# RodManipulator_SCH.net
KiCad netlist of a schematic drawn in Altium Designer
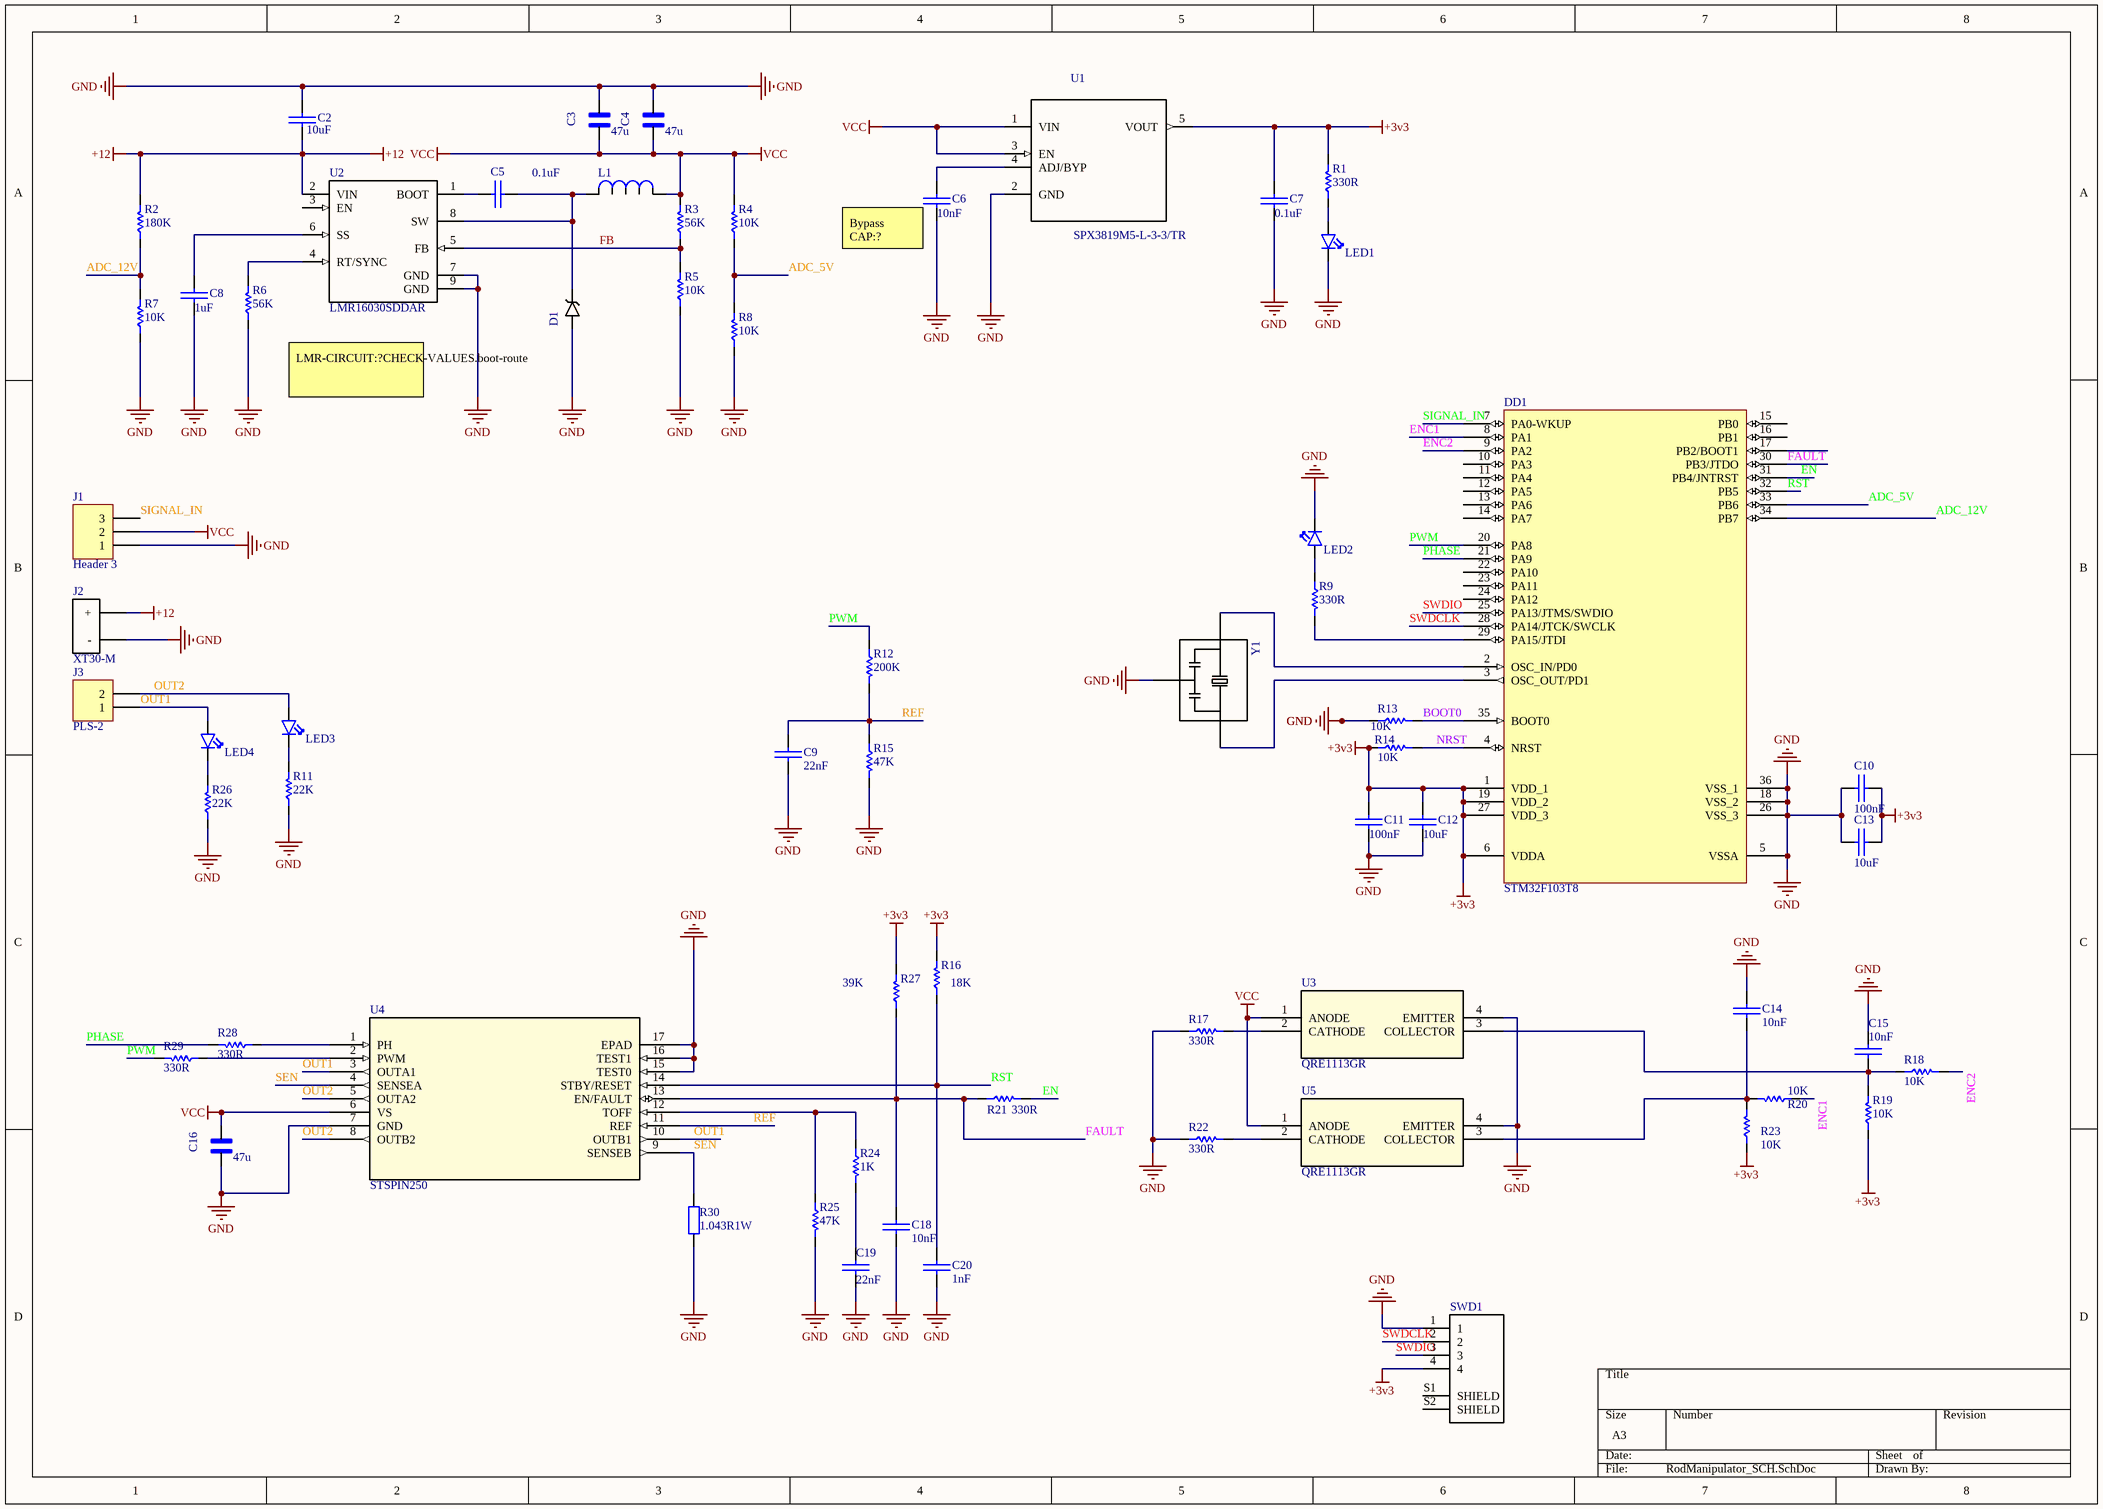
[diagram p0: RodManipulator_SCH.SchDoc]

(export (version "E")
  (design (tool "Eeschema 10.0.6"))
  (components
    (comp (ref "C2")
      (value "10uF")
      (footprint "SMD_CAP_0603")
      (description "Bipolar Capacitor")
      (fields (field (name "VOLTAGE") "100V") (field (name "DESIGNER") "Saeid Jorablo"))
      (libsource (lib "R2T Team Library") (part "Cap-Bipolar"))
    )
    (comp (ref "C3")
      (value "47u")
      (footprint "*CAPC3216X125N")
      (description "Multilayer Ceramic Capacitor, GRM Series, 47 - F, - 10%, X5R, 10 V, 1206 [3216 Metric]")
      (fields (field (name "MF") "Murata Electronics") (field (name "MP") "GRM31CR61A476KE15L"))
      (libsource (lib "lib") (part "GRM31CR61A476KE15L"))
    )
    (comp (ref "C4")
      (value "47u")
      (footprint "*CAPC3216X125N")
      (description "Multilayer Ceramic Capacitor, GRM Series, 47 - F, - 10%, X5R, 10 V, 1206 [3216 Metric]")
      (fields (field (name "MF") "Murata Electronics") (field (name "MP") "GRM31CR61A476KE15L"))
      (libsource (lib "lib") (part "GRM31CR61A476KE15L"))
    )
    (comp (ref "C5")
      (value "0.1uF")
      (footprint "SMD_CAP_0603")
      (description "Bipolar Capacitor")
      (fields (field (name "VOLTAGE") "100V") (field (name "DESIGNER") "Saeid Jorablo"))
      (libsource (lib "R2T Team Library") (part "Cap-Bipolar"))
    )
    (comp (ref "C6")
      (value "10nF")
      (footprint "SMD_CAP_0603")
      (description "Bipolar Capacitor")
      (fields (field (name "VOLTAGE") "100V") (field (name "DESIGNER") "Saeid Jorablo"))
      (libsource (lib "R2T Team Library") (part "Cap-Bipolar"))
    )
    (comp (ref "C7")
      (value "0.1uF")
      (footprint "SMD_CAP_0603")
      (description "Bipolar Capacitor")
      (fields (field (name "VOLTAGE") "100V") (field (name "DESIGNER") "Saeid Jorablo"))
      (libsource (lib "R2T Team Library") (part "Cap-Bipolar"))
    )
    (comp (ref "C8")
      (value "1uF")
      (footprint "SMD_CAP_0603")
      (description "Bipolar Capacitor")
      (fields (field (name "VOLTAGE") "100V") (field (name "DESIGNER") "Saeid Jorablo"))
      (libsource (lib "R2T Team Library") (part "Cap-Bipolar"))
    )
    (comp (ref "C9")
      (value "22nF")
      (footprint "SMD_CAP_0603")
      (description "Bipolar Capacitor")
      (fields (field (name "VOLTAGE") "100V") (field (name "DESIGNER") "Saeid Jorablo"))
      (libsource (lib "R2T Team Library") (part "Cap-Bipolar"))
    )
    (comp (ref "C10")
      (value "100nF")
      (footprint "SMD_CAP_0603")
      (description "Bipolar Capacitor")
      (fields (field (name "VOLTAGE") "100V") (field (name "DESIGNER") "Saeid Jorablo"))
      (libsource (lib "R2T Team Library") (part "Cap-Bipolar"))
    )
    (comp (ref "C11")
      (value "100nF")
      (footprint "SMD_CAP_0603")
      (description "Bipolar Capacitor")
      (fields (field (name "VOLTAGE") "100V") (field (name "DESIGNER") "Saeid Jorablo"))
      (libsource (lib "R2T Team Library") (part "Cap-Bipolar"))
    )
    (comp (ref "C12")
      (value "10uF")
      (footprint "SMD_CAP_0603")
      (description "Bipolar Capacitor")
      (fields (field (name "VOLTAGE") "100V") (field (name "DESIGNER") "Saeid Jorablo"))
      (libsource (lib "R2T Team Library") (part "Cap-Bipolar"))
    )
    (comp (ref "C13")
      (value "10uF")
      (footprint "SMD_CAP_0603")
      (description "Bipolar Capacitor")
      (fields (field (name "VOLTAGE") "100V") (field (name "DESIGNER") "Saeid Jorablo"))
      (libsource (lib "R2T Team Library") (part "Cap-Bipolar"))
    )
    (comp (ref "C14")
      (value "10nF")
      (footprint "SMD_CAP_0603")
      (description "Bipolar Capacitor")
      (fields (field (name "VOLTAGE") "100V") (field (name "DESIGNER") "Saeid Jorablo"))
      (libsource (lib "R2T Team Library") (part "Cap-Bipolar"))
    )
    (comp (ref "C15")
      (value "10nF")
      (footprint "SMD_CAP_0603")
      (description "Bipolar Capacitor")
      (fields (field (name "VOLTAGE") "100V") (field (name "DESIGNER") "Saeid Jorablo"))
      (libsource (lib "R2T Team Library") (part "Cap-Bipolar"))
    )
    (comp (ref "C16")
      (value "47u")
      (footprint "*CAPC3216X125N")
      (description "Multilayer Ceramic Capacitor, GRM Series, 47 - F, - 10%, X5R, 10 V, 1206 [3216 Metric]")
      (fields (field (name "MF") "Murata Electronics") (field (name "MP") "GRM31CR61A476KE15L"))
      (libsource (lib "lib") (part "GRM31CR61A476KE15L"))
    )
    (comp (ref "C18")
      (value "10nF")
      (footprint "SMD_CAP_0603")
      (description "Bipolar Capacitor")
      (fields (field (name "VOLTAGE") "100V") (field (name "DESIGNER") "Saeid Jorablo"))
      (libsource (lib "R2T Team Library") (part "Cap-Bipolar"))
    )
    (comp (ref "C19")
      (value "22nF")
      (footprint "SMD_CAP_0603")
      (description "Bipolar Capacitor")
      (fields (field (name "VOLTAGE") "100V") (field (name "DESIGNER") "Saeid Jorablo"))
      (libsource (lib "R2T Team Library") (part "Cap-Bipolar"))
    )
    (comp (ref "C20")
      (value "1nF")
      (footprint "SMD_CAP_0603")
      (description "Bipolar Capacitor")
      (fields (field (name "VOLTAGE") "100V") (field (name "DESIGNER") "Saeid Jorablo"))
      (libsource (lib "R2T Team Library") (part "Cap-Bipolar"))
    )
    (comp (ref "D1")
      (value "SK56")
      (footprint "*SMB_P6SMB62AT3G(Primary)")
      (description "Диод Шоттки 5А 60В [SMB / DO-214AA]")
      (fields (field (name "MF") "Littelfuse Inc."))
      (libsource (lib "lib") (part "SK56"))
    )
    (comp (ref "DD1")
      (value "STM32F103T8")
      (footprint "*QFN50P600X600X100-37N")
      (description "STM32F103T8U6, Микроконтроллер 32BIT ARM 64K FLASH [VFQFPN-36]")
      (fields (field (name "MF") "STM") (field (name "MP") "STM32F103T8U6"))
      (libsource (lib "lib") (part "STM32F103T8"))
    )
    (comp (ref "J1")
      (value "Header 3")
      (footprint "HDR Side 3 pin")
      (description "Header, 3-Pin")
      (fields (field (name "PUBLISHER") "Altium Limited"))
      (libsource (lib "lib") (part "Header 3"))
    )
    (comp (ref "J2")
      (value "XT30-M")
      (footprint "XT30-M side")
      (fields (field (name "MP") "XT60-M") (field (name "MF") "AMASS"))
      (libsource (lib "lib") (part "XT30-M"))
    )
    (comp (ref "J3")
      (value "PLS-2")
      (footprint "HDR Side 2 pin")
      (description "Header, 2-Pin")
      (fields (field (name "MF") "Connfly electronic (Zhenqin)") (field (name "MP") "PLS-3 (DS1021-1x3)"))
      (libsource (lib "lib") (part "PLS-2"))
    )
    (comp (ref "L1")
      (value "IHLP2020BZER100M01")
      (footprint "IHLP")
      (description "10µH Shielded Molded Inductor 2.3A 199mOhm Max Nonstandard")
      (fields (field (name "MF") "Vishay Dale"))
      (libsource (lib "lib") (part "IHLP2020BZER100M01"))
    )
    (comp (ref "LED1")
      (value "LED")
      (footprint "LED0603")
      (fields (field (name "DESIGNER :") "Razi Research Team Of Mashhad - Hamed Jafarzadeh"))
      (libsource (lib "R2T Team Library") (part "LED"))
    )
    (comp (ref "LED2")
      (value "LED")
      (footprint "LED0603")
      (fields (field (name "DESIGNER :") "Razi Research Team Of Mashhad - Hamed Jafarzadeh"))
      (libsource (lib "R2T Team Library") (part "LED"))
    )
    (comp (ref "LED3")
      (value "LED")
      (footprint "LED0603")
      (fields (field (name "DESIGNER :") "Razi Research Team Of Mashhad - Hamed Jafarzadeh"))
      (libsource (lib "R2T Team Library") (part "LED"))
    )
    (comp (ref "LED4")
      (value "LED")
      (footprint "LED0603")
      (fields (field (name "DESIGNER :") "Razi Research Team Of Mashhad - Hamed Jafarzadeh"))
      (libsource (lib "R2T Team Library") (part "LED"))
    )
    (comp (ref "R1")
      (value "330R")
      (footprint "RES 0603 (1608X06L)")
      (description "Resistor")
      (fields (field (name "TOLERANCE") "5%") (field (name "POWER") "1/8 W"))
      (libsource (lib "R2T Team Library") (part "Resistor"))
    )
    (comp (ref "R2")
      (value "180K")
      (footprint "RES 0603 (1608X06L)")
      (description "Resistor")
      (fields (field (name "TOLERANCE") "5%") (field (name "POWER") "1/8 W"))
      (libsource (lib "R2T Team Library") (part "Resistor"))
    )
    (comp (ref "R3")
      (value "56K")
      (footprint "RES 0603 (1608X06L)")
      (description "Resistor")
      (fields (field (name "TOLERANCE") "5%") (field (name "POWER") "1/8 W"))
      (libsource (lib "R2T Team Library") (part "Resistor"))
    )
    (comp (ref "R4")
      (value "10K")
      (footprint "RES 0603 (1608X06L)")
      (description "Resistor")
      (fields (field (name "TOLERANCE") "5%") (field (name "POWER") "1/8 W"))
      (libsource (lib "R2T Team Library") (part "Resistor"))
    )
    (comp (ref "R5")
      (value "10K")
      (footprint "RES 0603 (1608X06L)")
      (description "Resistor")
      (fields (field (name "TOLERANCE") "5%") (field (name "POWER") "1/8 W"))
      (libsource (lib "R2T Team Library") (part "Resistor"))
    )
    (comp (ref "R6")
      (value "56K")
      (footprint "RES 0603 (1608X06L)")
      (description "Resistor")
      (fields (field (name "TOLERANCE") "5%") (field (name "POWER") "1/8 W"))
      (libsource (lib "R2T Team Library") (part "Resistor"))
    )
    (comp (ref "R7")
      (value "10K")
      (footprint "RES 0603 (1608X06L)")
      (description "Resistor")
      (fields (field (name "TOLERANCE") "5%") (field (name "POWER") "1/8 W"))
      (libsource (lib "R2T Team Library") (part "Resistor"))
    )
    (comp (ref "R8")
      (value "10K")
      (footprint "RES 0603 (1608X06L)")
      (description "Resistor")
      (fields (field (name "TOLERANCE") "5%") (field (name "POWER") "1/8 W"))
      (libsource (lib "R2T Team Library") (part "Resistor"))
    )
    (comp (ref "R9")
      (value "330R")
      (footprint "RES 0603 (1608X06L)")
      (description "Resistor")
      (fields (field (name "TOLERANCE") "5%") (field (name "POWER") "1/8 W"))
      (libsource (lib "R2T Team Library") (part "Resistor"))
    )
    (comp (ref "R11")
      (value "22K")
      (footprint "RES 0603 (1608X06L)")
      (description "Resistor")
      (fields (field (name "TOLERANCE") "5%") (field (name "POWER") "1/8 W"))
      (libsource (lib "R2T Team Library") (part "Resistor"))
    )
    (comp (ref "R12")
      (value "200K")
      (footprint "RES 0603 (1608X06L)")
      (description "Resistor")
      (fields (field (name "TOLERANCE") "5%") (field (name "POWER") "1/8 W"))
      (libsource (lib "R2T Team Library") (part "Resistor"))
    )
    (comp (ref "R13")
      (value "10K")
      (footprint "RES 0603 (1608X06L)")
      (description "Resistor")
      (fields (field (name "TOLERANCE") "5%") (field (name "POWER") "1/8 W"))
      (libsource (lib "R2T Team Library") (part "Resistor"))
    )
    (comp (ref "R14")
      (value "10K")
      (footprint "RES 0603 (1608X06L)")
      (description "Resistor")
      (fields (field (name "TOLERANCE") "5%") (field (name "POWER") "1/8 W"))
      (libsource (lib "R2T Team Library") (part "Resistor"))
    )
    (comp (ref "R15")
      (value "47K")
      (footprint "RES 0603 (1608X06L)")
      (description "Resistor")
      (fields (field (name "TOLERANCE") "5%") (field (name "POWER") "1/8 W"))
      (libsource (lib "R2T Team Library") (part "Resistor"))
    )
    (comp (ref "R16")
      (value "18K")
      (footprint "RES 0603 (1608X06L)")
      (description "Resistor")
      (fields (field (name "TOLERANCE") "5%") (field (name "POWER") "1/8 W"))
      (libsource (lib "R2T Team Library") (part "Resistor"))
    )
    (comp (ref "R17")
      (value "330R")
      (footprint "RES 0603 (1608X06L)")
      (description "Resistor")
      (fields (field (name "TOLERANCE") "5%") (field (name "POWER") "1/8 W"))
      (libsource (lib "R2T Team Library") (part "Resistor"))
    )
    (comp (ref "R18")
      (value "10K")
      (footprint "RES 0603 (1608X06L)")
      (description "Resistor")
      (fields (field (name "TOLERANCE") "5%") (field (name "POWER") "1/8 W"))
      (libsource (lib "R2T Team Library") (part "Resistor"))
    )
    (comp (ref "R19")
      (value "10K")
      (footprint "RES 0603 (1608X06L)")
      (description "Resistor")
      (fields (field (name "TOLERANCE") "5%") (field (name "POWER") "1/8 W"))
      (libsource (lib "R2T Team Library") (part "Resistor"))
    )
    (comp (ref "R20")
      (value "10K")
      (footprint "RES 0603 (1608X06L)")
      (description "Resistor")
      (fields (field (name "TOLERANCE") "5%") (field (name "POWER") "1/8 W"))
      (libsource (lib "R2T Team Library") (part "Resistor"))
    )
    (comp (ref "R21")
      (value "330R")
      (footprint "RES 0603 (1608X06L)")
      (description "Resistor")
      (fields (field (name "TOLERANCE") "5%") (field (name "POWER") "1/8 W"))
      (libsource (lib "R2T Team Library") (part "Resistor"))
    )
    (comp (ref "R22")
      (value "330R")
      (footprint "RES 0603 (1608X06L)")
      (description "Resistor")
      (fields (field (name "TOLERANCE") "5%") (field (name "POWER") "1/8 W"))
      (libsource (lib "R2T Team Library") (part "Resistor"))
    )
    (comp (ref "R23")
      (value "10K")
      (footprint "RES 0603 (1608X06L)")
      (description "Resistor")
      (fields (field (name "TOLERANCE") "5%") (field (name "POWER") "1/8 W"))
      (libsource (lib "R2T Team Library") (part "Resistor"))
    )
    (comp (ref "R24")
      (value "1K")
      (footprint "RES 0603 (1608X06L)")
      (description "Resistor")
      (fields (field (name "TOLERANCE") "5%") (field (name "POWER") "1/8 W"))
      (libsource (lib "R2T Team Library") (part "Resistor"))
    )
    (comp (ref "R25")
      (value "47K")
      (footprint "RES 0603 (1608X06L)")
      (description "Resistor")
      (fields (field (name "TOLERANCE") "5%") (field (name "POWER") "1/8 W"))
      (libsource (lib "R2T Team Library") (part "Resistor"))
    )
    (comp (ref "R26")
      (value "22K")
      (footprint "RES 0603 (1608X06L)")
      (description "Resistor")
      (fields (field (name "TOLERANCE") "5%") (field (name "POWER") "1/8 W"))
      (libsource (lib "R2T Team Library") (part "Resistor"))
    )
    (comp (ref "R27")
      (value "39K")
      (footprint "RES 0603 (1608X06L)")
      (description "Resistor")
      (fields (field (name "TOLERANCE") "5%") (field (name "POWER") "1/8 W"))
      (libsource (lib "R2T Team Library") (part "Resistor"))
    )
    (comp (ref "R28")
      (value "330R")
      (footprint "RES 0603 (1608X06L)")
      (description "Resistor")
      (fields (field (name "TOLERANCE") "5%") (field (name "POWER") "1/8 W"))
      (libsource (lib "R2T Team Library") (part "Resistor"))
    )
    (comp (ref "R29")
      (value "330R")
      (footprint "RES 0603 (1608X06L)")
      (description "Resistor")
      (fields (field (name "TOLERANCE") "5%") (field (name "POWER") "1/8 W"))
      (libsource (lib "R2T Team Library") (part "Resistor"))
    )
    (comp (ref "R30")
      (value "1.043R1W")
      (footprint "RES2512")
      (description "Resistor")
      (fields (field (name "Comment") "resistor") (field (name "PUBLISHER") "Altium Limited"))
      (libsource (lib "lib") (part "resistor"))
    )
    (comp (ref "SWD1")
      (value "SM04B-GHS-TB(LF)(SN)-")
      (footprint "JST_BM04B-GHS-holes")
      (description "Conn Shrouded Header HDR 4 POS 1.25mm Solder ST SMD Reel")
      (fields (field (name "MF") "JST Sales") (field (name "MP") "SM04B-GHS-TB(LF)(SN)"))
      (libsource (lib "lib") (part "SWD SM04B-GHS-TB(LF)(SN)-"))
    )
    (comp (ref "U1")
      (value "SPX3819M5-L-3-3/TR")
      (footprint "*SOT95P280X145-5N")
      (description "Low Dropout Voltage Regulator, Adjustable 0.5A, В±1%, 2.5 to 16 Vin, 5-Pin SOT-23")
      (fields (field (name "MF") "MaxLinear, Inc."))
      (libsource (lib "lib") (part "SPX3819M5-L-3-3/TR"))
    )
    (comp (ref "U2")
      (value "LMR16030SDDAR")
      (footprint "*SOIC127P600X170-9N - duplicate")
      (fields (field (name "MF") "Texas Instruments"))
      (libsource (lib "lib") (part "LMR16030SDDAR"))
    )
    (comp (ref "U3")
      (value "QRE1113GR")
      (footprint "SMD4_2P90X3P60_ONS")
      (description "No Description Available")
      (fields (field (name "COPYRIGHT") "Copyright (C) 2018 Accelerated Designs. All rights reserved"))
      (libsource (lib "lib") (part "QRE1113GR"))
    )
    (comp (ref "U4")
      (value "STSPIN250")
      (footprint "VFQFPN-16")
      (description "No Description Available")
      (fields
        (field (name "MANUFACTURER_PART_NUMBER") "STSPIN220")
        (field (name "COPYRIGHT") "Copyright (C) 2018 Accelerated Designs. All rights reserved")
      )
      (libsource (lib "lib") (part "STSPIN250"))
    )
    (comp (ref "U5")
      (value "QRE1113GR")
      (footprint "SMD4_2P90X3P60_ONS")
      (description "No Description Available")
      (fields (field (name "COPYRIGHT") "Copyright (C) 2018 Accelerated Designs. All rights reserved"))
      (libsource (lib "lib") (part "QRE1113GR"))
    )
    (comp (ref "Y1")
      (value "CSTCE8M00G55-R0")
      (footprint "*OSC_CSTCE8M00G55-R0")
      (description "Ceramic Resonator 8MHz ??0.5% _Tol_ ??0.2% _Stability_ 33pF 40Ohm 3-Pin CSMD T/R")
      (fields (field (name "MF") "Murata"))
      (libsource (lib "lib") (part "CSTCE8M00G55-R0"))
    )
  )
  (nets
    (net (code "1") (name "+3v3") (class "Default")
      (node (ref "C10") (pin "1") (pinfunction "+_1") (pintype "passive"))
      (node (ref "C11") (pin "1") (pinfunction "+_1") (pintype "passive"))
      (node (ref "C12") (pin "1") (pinfunction "+_1") (pintype "passive"))
      (node (ref "C13") (pin "1") (pinfunction "+_1") (pintype "passive"))
      (node (ref "C7") (pin "2") (pinfunction "-_2") (pintype "passive"))
      (node (ref "DD1") (pin "1") (pinfunction "VDD_1_1") (pintype "power_in"))
      (node (ref "DD1") (pin "19") (pinfunction "VDD_2_19") (pintype "power_in"))
      (node (ref "DD1") (pin "27") (pinfunction "VDD_3_27") (pintype "power_in"))
      (node (ref "DD1") (pin "6") (pinfunction "VDDA_6") (pintype "power_in"))
      (node (ref "R1") (pin "2") (pinfunction "2_2") (pintype "passive"))
      (node (ref "R14") (pin "1") (pinfunction "1_1") (pintype "passive"))
      (node (ref "R16") (pin "2") (pinfunction "2_2") (pintype "passive"))
      (node (ref "R19") (pin "1") (pinfunction "1_1") (pintype "passive"))
      (node (ref "R23") (pin "1") (pinfunction "1_1") (pintype "passive"))
      (node (ref "R27") (pin "2") (pinfunction "2_2") (pintype "passive"))
      (node (ref "SWD1") (pin "4") (pinfunction "4_4") (pintype "passive"))
      (node (ref "U1") (pin "5") (pinfunction "VOUT_5") (pintype "output"))
    )
    (net (code "2") (name "+12") (class "Default")
      (node (ref "C2") (pin "1") (pinfunction "+_1") (pintype "passive"))
      (node (ref "J2") (pin "PLUS") (pinfunction "+_PLUS") (pintype "passive"))
      (node (ref "R2") (pin "2") (pinfunction "2_2") (pintype "passive"))
      (node (ref "U2") (pin "2") (pinfunction "VIN_2") (pintype "power_in"))
    )
    (net (code "3") (name "/ADC_5V") (class "Default")
      (node (ref "DD1") (pin "33") (pinfunction "PB6_33") (pintype "bidirectional"))
      (node (ref "R4") (pin "1") (pinfunction "1_1") (pintype "passive"))
      (node (ref "R8") (pin "2") (pinfunction "2_2") (pintype "passive"))
    )
    (net (code "4") (name "/ADC_12V") (class "Default")
      (node (ref "DD1") (pin "34") (pinfunction "PB7_34") (pintype "bidirectional"))
      (node (ref "R2") (pin "1") (pinfunction "1_1") (pintype "passive"))
      (node (ref "R7") (pin "2") (pinfunction "2_2") (pintype "passive"))
    )
    (net (code "5") (name "/BOOT0") (class "Default")
      (node (ref "DD1") (pin "35") (pinfunction "BOOT0_35") (pintype "input"))
      (node (ref "R13") (pin "2") (pinfunction "2_2") (pintype "passive"))
    )
    (net (code "6") (name "/EN") (class "Default")
      (node (ref "DD1") (pin "31") (pinfunction "PB4/JNTRST_31") (pintype "bidirectional"))
      (node (ref "R21") (pin "2") (pinfunction "2_2") (pintype "passive"))
    )
    (net (code "7") (name "/ENC1") (class "Default")
      (node (ref "DD1") (pin "8") (pinfunction "PA1_8") (pintype "bidirectional"))
      (node (ref "R20") (pin "1") (pinfunction "1_1") (pintype "passive"))
    )
    (net (code "8") (name "/ENC2") (class "Default")
      (node (ref "DD1") (pin "9") (pinfunction "PA2_9") (pintype "bidirectional"))
      (node (ref "R18") (pin "2") (pinfunction "2_2") (pintype "passive"))
    )
    (net (code "9") (name "/FAULT") (class "Default")
      (node (ref "C18") (pin "2") (pinfunction "-_2") (pintype "passive"))
      (node (ref "DD1") (pin "30") (pinfunction "PB3/JTDO_30") (pintype "bidirectional"))
      (node (ref "R21") (pin "1") (pinfunction "1_1") (pintype "passive"))
      (node (ref "R27") (pin "1") (pinfunction "1_1") (pintype "passive"))
      (node (ref "U4") (pin "13") (pinfunction "EN/FAULT_13") (pintype "bidirectional"))
    )
    (net (code "10") (name "/FB") (class "Default")
      (node (ref "R3") (pin "1") (pinfunction "1_1") (pintype "passive"))
      (node (ref "R5") (pin "2") (pinfunction "2_2") (pintype "passive"))
      (node (ref "U2") (pin "5") (pinfunction "FB_5") (pintype "input"))
    )
    (net (code "11") (name "/NRST") (class "Default")
      (node (ref "DD1") (pin "4") (pinfunction "NRST_4") (pintype "bidirectional"))
      (node (ref "R14") (pin "2") (pinfunction "2_2") (pintype "passive"))
    )
    (net (code "12") (name "/OUT1") (class "Default")
      (node (ref "J3") (pin "1") (pinfunction "1_1") (pintype "passive"))
      (node (ref "LED4") (pin "1") (pinfunction "A_1") (pintype "passive"))
      (node (ref "U4") (pin "10") (pinfunction "OUTB1_10") (pintype "output"))
      (node (ref "U4") (pin "3") (pinfunction "OUTA1_3") (pintype "output"))
    )
    (net (code "13") (name "/OUT2") (class "Default")
      (node (ref "J3") (pin "2") (pinfunction "2_2") (pintype "passive"))
      (node (ref "LED3") (pin "1") (pinfunction "A_1") (pintype "passive"))
      (node (ref "U4") (pin "5") (pinfunction "OUTA2_5") (pintype "output"))
      (node (ref "U4") (pin "8") (pinfunction "OUTB2_8") (pintype "output"))
    )
    (net (code "14") (name "/PHASE") (class "Default")
      (node (ref "DD1") (pin "21") (pinfunction "PA9_21") (pintype "bidirectional"))
      (node (ref "R28") (pin "2") (pinfunction "2_2") (pintype "passive"))
    )
    (net (code "15") (name "/PWM") (class "Default")
      (node (ref "DD1") (pin "20") (pinfunction "PA8_20") (pintype "bidirectional"))
      (node (ref "R12") (pin "1") (pinfunction "1_1") (pintype "passive"))
      (node (ref "R29") (pin "2") (pinfunction "2_2") (pintype "passive"))
    )
    (net (code "16") (name "/REF") (class "Default")
      (node (ref "C9") (pin "2") (pinfunction "-_2") (pintype "passive"))
      (node (ref "R12") (pin "2") (pinfunction "2_2") (pintype "passive"))
      (node (ref "R15") (pin "1") (pinfunction "1_1") (pintype "passive"))
      (node (ref "U4") (pin "11") (pinfunction "REF_11") (pintype "input"))
    )
    (net (code "17") (name "/RST") (class "Default")
      (node (ref "C20") (pin "2") (pinfunction "-_2") (pintype "passive"))
      (node (ref "DD1") (pin "32") (pinfunction "PB5_32") (pintype "bidirectional"))
      (node (ref "R16") (pin "1") (pinfunction "1_1") (pintype "passive"))
      (node (ref "U4") (pin "14") (pinfunction "STBY/RESET_14") (pintype "input"))
    )
    (net (code "18") (name "/SEN") (class "Default")
      (node (ref "R30") (pin "2") (pinfunction "2_2") (pintype "passive"))
      (node (ref "U4") (pin "4") (pinfunction "SENSEA_4") (pintype "output"))
      (node (ref "U4") (pin "9") (pinfunction "SENSEB_9") (pintype "output"))
    )
    (net (code "19") (name "/SIGNAL_IN") (class "Default")
      (node (ref "DD1") (pin "7") (pinfunction "PA0-WKUP_7") (pintype "bidirectional"))
      (node (ref "J1") (pin "3") (pinfunction "3_3") (pintype "passive"))
    )
    (net (code "20") (name "/SWDCLK") (class "Default")
      (node (ref "DD1") (pin "28") (pinfunction "PA14/JTCK/SWCLK_28") (pintype "bidirectional"))
      (node (ref "SWD1") (pin "2") (pinfunction "2_2") (pintype "passive"))
    )
    (net (code "21") (name "/SWDIO") (class "Default")
      (node (ref "DD1") (pin "25") (pinfunction "PA13/JTMS/SWDIO_25") (pintype "bidirectional"))
      (node (ref "SWD1") (pin "3") (pinfunction "3_3") (pintype "passive"))
    )
    (net (code "22") (name "GND") (class "Default")
      (node (ref "C10") (pin "2") (pinfunction "-_2") (pintype "passive"))
      (node (ref "C11") (pin "2") (pinfunction "-_2") (pintype "passive"))
      (node (ref "C12") (pin "2") (pinfunction "-_2") (pintype "passive"))
      (node (ref "C13") (pin "2") (pinfunction "-_2") (pintype "passive"))
      (node (ref "C14") (pin "1") (pinfunction "+_1") (pintype "passive"))
      (node (ref "C15") (pin "1") (pinfunction "+_1") (pintype "passive"))
      (node (ref "C16") (pin "1") (pinfunction "1_1") (pintype "passive"))
      (node (ref "C18") (pin "1") (pinfunction "+_1") (pintype "passive"))
      (node (ref "C19") (pin "2") (pinfunction "-_2") (pintype "passive"))
      (node (ref "C2") (pin "2") (pinfunction "-_2") (pintype "passive"))
      (node (ref "C20") (pin "1") (pinfunction "+_1") (pintype "passive"))
      (node (ref "C3") (pin "2") (pinfunction "2_2") (pintype "passive"))
      (node (ref "C4") (pin "2") (pinfunction "2_2") (pintype "passive"))
      (node (ref "C6") (pin "1") (pinfunction "+_1") (pintype "passive"))
      (node (ref "C7") (pin "1") (pinfunction "+_1") (pintype "passive"))
      (node (ref "C8") (pin "2") (pinfunction "-_2") (pintype "passive"))
      (node (ref "C9") (pin "1") (pinfunction "+_1") (pintype "passive"))
      (node (ref "D1") (pin "A") (pinfunction "A_A") (pintype "power_in"))
      (node (ref "DD1") (pin "18") (pinfunction "VSS_2_18") (pintype "power_in"))
      (node (ref "DD1") (pin "26") (pinfunction "VSS_3_26") (pintype "power_in"))
      (node (ref "DD1") (pin "36") (pinfunction "VSS_1_36") (pintype "power_in"))
      (node (ref "DD1") (pin "5") (pinfunction "VSSA_5") (pintype "power_in"))
      (node (ref "J1") (pin "1") (pinfunction "1_1") (pintype "passive"))
      (node (ref "J2") (pin "MINUS") (pinfunction "-_MINUS") (pintype "passive"))
      (node (ref "LED1") (pin "2") (pinfunction "K_2") (pintype "passive"))
      (node (ref "LED2") (pin "2") (pinfunction "K_2") (pintype "passive"))
      (node (ref "R11") (pin "1") (pinfunction "1_1") (pintype "passive"))
      (node (ref "R13") (pin "1") (pinfunction "1_1") (pintype "passive"))
      (node (ref "R15") (pin "2") (pinfunction "2_2") (pintype "passive"))
      (node (ref "R17") (pin "1") (pinfunction "1_1") (pintype "passive"))
      (node (ref "R22") (pin "1") (pinfunction "1_1") (pintype "passive"))
      (node (ref "R25") (pin "2") (pinfunction "2_2") (pintype "passive"))
      (node (ref "R26") (pin "1") (pinfunction "1_1") (pintype "passive"))
      (node (ref "R30") (pin "1") (pinfunction "1_1") (pintype "passive"))
      (node (ref "R5") (pin "1") (pinfunction "1_1") (pintype "passive"))
      (node (ref "R6") (pin "1") (pinfunction "1_1") (pintype "passive"))
      (node (ref "R7") (pin "1") (pinfunction "1_1") (pintype "passive"))
      (node (ref "R8") (pin "1") (pinfunction "1_1") (pintype "passive"))
      (node (ref "SWD1") (pin "1") (pinfunction "1_1") (pintype "passive"))
      (node (ref "U1") (pin "2") (pinfunction "GND_2") (pintype "passive"))
      (node (ref "U2") (pin "7") (pinfunction "GND_7") (pintype "power_in"))
      (node (ref "U2") (pin "9") (pinfunction "GND_9") (pintype "power_in"))
      (node (ref "U3") (pin "4") (pinfunction "EMITTER_4") (pintype "passive"))
      (node (ref "U4") (pin "15") (pinfunction "TEST0_15") (pintype "input"))
      (node (ref "U4") (pin "16") (pinfunction "TEST1_16") (pintype "input"))
      (node (ref "U4") (pin "17") (pinfunction "EPAD_17") (pintype "passive"))
      (node (ref "U4") (pin "7") (pinfunction "GND_7") (pintype "power_in"))
      (node (ref "U5") (pin "4") (pinfunction "EMITTER_4") (pintype "passive"))
      (node (ref "Y1") (pin "2") (pinfunction "2_2") (pintype "power_in"))
    )
    (net (code "23") (name "Net-(C5-+)") (class "Default")
      (node (ref "C5") (pin "1") (pinfunction "+_1") (pintype "passive"))
      (node (ref "D1") (pin "C") (pinfunction "C_C") (pintype "power_in"))
      (node (ref "L1") (pin "2") (pinfunction "2_2") (pintype "passive"))
      (node (ref "U2") (pin "8") (pinfunction "SW_8") (pintype "power_in"))
    )
    (net (code "24") (name "Net-(C5--)") (class "Default")
      (node (ref "C5") (pin "2") (pinfunction "-_2") (pintype "passive"))
      (node (ref "U2") (pin "1") (pinfunction "BOOT_1") (pintype "power_in"))
    )
    (net (code "25") (name "Net-(C6--)") (class "Default")
      (node (ref "C6") (pin "2") (pinfunction "-_2") (pintype "passive"))
      (node (ref "U1") (pin "4") (pinfunction "ADJ/BYP_4") (pintype "passive"))
    )
    (net (code "26") (name "Net-(C8-+)") (class "Default")
      (node (ref "C8") (pin "1") (pinfunction "+_1") (pintype "passive"))
      (node (ref "U2") (pin "6") (pinfunction "SS_6") (pintype "input"))
    )
    (net (code "27") (name "Net-(C14--)") (class "Default")
      (node (ref "C14") (pin "2") (pinfunction "-_2") (pintype "passive"))
      (node (ref "R20") (pin "2") (pinfunction "2_2") (pintype "passive"))
      (node (ref "R23") (pin "2") (pinfunction "2_2") (pintype "passive"))
      (node (ref "U5") (pin "3") (pinfunction "COLLECTOR_3") (pintype "passive"))
    )
    (net (code "28") (name "Net-(C15--)") (class "Default")
      (node (ref "C15") (pin "2") (pinfunction "-_2") (pintype "passive"))
      (node (ref "R18") (pin "1") (pinfunction "1_1") (pintype "passive"))
      (node (ref "R19") (pin "2") (pinfunction "2_2") (pintype "passive"))
      (node (ref "U3") (pin "3") (pinfunction "COLLECTOR_3") (pintype "passive"))
    )
    (net (code "29") (name "Net-(C19-+)") (class "Default")
      (node (ref "C19") (pin "1") (pinfunction "+_1") (pintype "passive"))
      (node (ref "R24") (pin "2") (pinfunction "2_2") (pintype "passive"))
    )
    (net (code "30") (name "Net-(DD1-OSC_IN{slash}PD0)") (class "Default")
      (node (ref "DD1") (pin "2") (pinfunction "OSC_IN/PD0_2") (pintype "input"))
      (node (ref "Y1") (pin "1") (pinfunction "1_1") (pintype "passive"))
    )
    (net (code "31") (name "Net-(DD1-OSC_OUT{slash}PD1)") (class "Default")
      (node (ref "DD1") (pin "3") (pinfunction "OSC_OUT/PD1_3") (pintype "output"))
      (node (ref "Y1") (pin "3") (pinfunction "3_3") (pintype "passive"))
    )
    (net (code "32") (name "Net-(DD1-PA15{slash}JTDI)") (class "Default")
      (node (ref "DD1") (pin "29") (pinfunction "PA15/JTDI_29") (pintype "bidirectional"))
      (node (ref "R9") (pin "2") (pinfunction "2_2") (pintype "passive"))
    )
    (net (code "33") (name "Net-(LED1-A)") (class "Default")
      (node (ref "LED1") (pin "1") (pinfunction "A_1") (pintype "passive"))
      (node (ref "R1") (pin "1") (pinfunction "1_1") (pintype "passive"))
    )
    (net (code "34") (name "Net-(LED2-A)") (class "Default")
      (node (ref "LED2") (pin "1") (pinfunction "A_1") (pintype "passive"))
      (node (ref "R9") (pin "1") (pinfunction "1_1") (pintype "passive"))
    )
    (net (code "35") (name "Net-(LED3-K)") (class "Default")
      (node (ref "LED3") (pin "2") (pinfunction "K_2") (pintype "passive"))
      (node (ref "R11") (pin "2") (pinfunction "2_2") (pintype "passive"))
    )
    (net (code "36") (name "Net-(LED4-K)") (class "Default")
      (node (ref "LED4") (pin "2") (pinfunction "K_2") (pintype "passive"))
      (node (ref "R26") (pin "2") (pinfunction "2_2") (pintype "passive"))
    )
    (net (code "37") (name "Net-(U2-RT{slash}SYNC)") (class "Default")
      (node (ref "R6") (pin "2") (pinfunction "2_2") (pintype "passive"))
      (node (ref "U2") (pin "4") (pinfunction "RT/SYNC_4") (pintype "input"))
    )
    (net (code "38") (name "Net-(U3-CATHODE)") (class "Default")
      (node (ref "R17") (pin "2") (pinfunction "2_2") (pintype "passive"))
      (node (ref "U3") (pin "2") (pinfunction "CATHODE_2") (pintype "passive"))
    )
    (net (code "39") (name "Net-(U4-PH)") (class "Default")
      (node (ref "R28") (pin "1") (pinfunction "1_1") (pintype "passive"))
      (node (ref "U4") (pin "1") (pinfunction "PH_1") (pintype "input"))
    )
    (net (code "40") (name "Net-(U4-PWM)") (class "Default")
      (node (ref "R29") (pin "1") (pinfunction "1_1") (pintype "passive"))
      (node (ref "U4") (pin "2") (pinfunction "PWM_2") (pintype "input"))
    )
    (net (code "41") (name "Net-(U4-TOFF)") (class "Default")
      (node (ref "R24") (pin "1") (pinfunction "1_1") (pintype "passive"))
      (node (ref "R25") (pin "1") (pinfunction "1_1") (pintype "passive"))
      (node (ref "U4") (pin "12") (pinfunction "TOFF_12") (pintype "input"))
    )
    (net (code "42") (name "Net-(U5-CATHODE)") (class "Default")
      (node (ref "R22") (pin "2") (pinfunction "2_2") (pintype "passive"))
      (node (ref "U5") (pin "2") (pinfunction "CATHODE_2") (pintype "passive"))
    )
    (net (code "43") (name "VCC") (class "Default")
      (node (ref "C16") (pin "2") (pinfunction "2_2") (pintype "passive"))
      (node (ref "C3") (pin "1") (pinfunction "1_1") (pintype "passive"))
      (node (ref "C4") (pin "1") (pinfunction "1_1") (pintype "passive"))
      (node (ref "J1") (pin "2") (pinfunction "2_2") (pintype "passive"))
      (node (ref "L1") (pin "1") (pinfunction "1_1") (pintype "passive"))
      (node (ref "R3") (pin "2") (pinfunction "2_2") (pintype "passive"))
      (node (ref "R4") (pin "2") (pinfunction "2_2") (pintype "passive"))
      (node (ref "U1") (pin "1") (pinfunction "VIN_1") (pintype "power_in"))
      (node (ref "U1") (pin "3") (pinfunction "EN_3") (pintype "input"))
      (node (ref "U3") (pin "1") (pinfunction "ANODE_1") (pintype "passive"))
      (node (ref "U4") (pin "6") (pinfunction "VS_6") (pintype "power_in"))
      (node (ref "U5") (pin "1") (pinfunction "ANODE_1") (pintype "passive"))
    )
    (net (code "44") (name "unconnected-(DD1-PA3-Pad10)") (class "Default")
      (node (ref "DD1") (pin "10") (pinfunction "PA3_10") (pintype "bidirectional"))
    )
    (net (code "45") (name "unconnected-(DD1-PA4-Pad11)") (class "Default")
      (node (ref "DD1") (pin "11") (pinfunction "PA4_11") (pintype "bidirectional"))
    )
    (net (code "46") (name "unconnected-(DD1-PA5-Pad12)") (class "Default")
      (node (ref "DD1") (pin "12") (pinfunction "PA5_12") (pintype "bidirectional"))
    )
    (net (code "47") (name "unconnected-(DD1-PA6-Pad13)") (class "Default")
      (node (ref "DD1") (pin "13") (pinfunction "PA6_13") (pintype "bidirectional"))
    )
    (net (code "48") (name "unconnected-(DD1-PA7-Pad14)") (class "Default")
      (node (ref "DD1") (pin "14") (pinfunction "PA7_14") (pintype "bidirectional"))
    )
    (net (code "49") (name "unconnected-(DD1-PA10-Pad22)") (class "Default")
      (node (ref "DD1") (pin "22") (pinfunction "PA10_22") (pintype "bidirectional"))
    )
    (net (code "50") (name "unconnected-(DD1-PA11-Pad23)") (class "Default")
      (node (ref "DD1") (pin "23") (pinfunction "PA11_23") (pintype "bidirectional"))
    )
    (net (code "51") (name "unconnected-(DD1-PA12-Pad24)") (class "Default")
      (node (ref "DD1") (pin "24") (pinfunction "PA12_24") (pintype "bidirectional"))
    )
    (net (code "52") (name "unconnected-(DD1-PB0-Pad15)") (class "Default")
      (node (ref "DD1") (pin "15") (pinfunction "PB0_15") (pintype "bidirectional"))
    )
    (net (code "53") (name "unconnected-(DD1-PB1-Pad16)") (class "Default")
      (node (ref "DD1") (pin "16") (pinfunction "PB1_16") (pintype "bidirectional"))
    )
    (net (code "54") (name "unconnected-(DD1-PB2{slash}BOOT1-Pad17)") (class "Default")
      (node (ref "DD1") (pin "17") (pinfunction "PB2/BOOT1_17") (pintype "bidirectional"))
    )
    (net (code "55") (name "unconnected-(SWD1-SHIELD-PadS1)") (class "Default")
      (node (ref "SWD1") (pin "S1") (pinfunction "SHIELD_S1") (pintype "passive"))
    )
    (net (code "56") (name "unconnected-(SWD1-SHIELD-PadS2)") (class "Default")
      (node (ref "SWD1") (pin "S2") (pinfunction "SHIELD_S2") (pintype "passive"))
    )
    (net (code "57") (name "unconnected-(U2-EN-Pad3)") (class "Default")
      (node (ref "U2") (pin "3") (pinfunction "EN_3") (pintype "input"))
    )
  )
)
